# 7-Gyroscope.net
KiCad netlist of a schematic drawn in Altium Designer
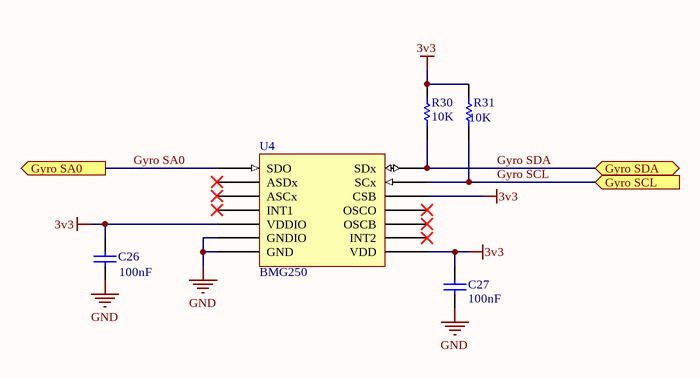
[diagram p0: 7-Gyroscope.SchDoc]

(export (version "E")
  (design (tool "Eeschema 10.0.6"))
  (components
    (comp (ref "C26")
      (value "100nF")
      (footprint "CAPC1608X90X30ML10T20")
      (description "Chip Capacitor, 100 nF, +/- 10%, 50 V, -55 to 125 degC, 0603 (1608 Metric), RoHS, Tape and Reel")
      (fields (field (name "VOLTAGE") "50Vdc") (field (name "MANUFACTURER") "SamsungElectro-Mechanics"))
      (libsource (lib "Altium Content Vault") (part "CAP-NP-2"))
    )
    (comp (ref "C27")
      (value "100nF")
      (footprint "CAPC1608X90X30ML10T20")
      (description "Chip Capacitor, 100 nF, +/- 10%, 50 V, -55 to 125 degC, 0603 (1608 Metric), RoHS, Tape and Reel")
      (fields (field (name "VOLTAGE") "50Vdc") (field (name "MANUFACTURER") "SamsungElectro-Mechanics"))
      (libsource (lib "Altium Content Vault") (part "CAP-NP-2"))
    )
    (comp (ref "R30")
      (value "10K")
      (footprint "RESC0603(1608)_N")
      (description "10K 0.1W 5% 0603 (1608 Metric)  SMD")
      (fields (field (name "TOLERANCE") "5 %") (field (name "POWER") "0.1 W"))
      (libsource (lib "Altium Content Vault") (part "RES"))
    )
    (comp (ref "R31")
      (value "10K")
      (footprint "RESC0603(1608)_N")
      (description "10K 0.1W 5% 0603 (1608 Metric)  SMD")
      (fields (field (name "TOLERANCE") "5 %") (field (name "POWER") "0.1 W"))
      (libsource (lib "Altium Content Vault") (part "RES"))
    )
    (comp (ref "U4")
      (value "BMG250")
      (footprint "BMG250")
      (description "3 Axis Gyroscope")
      (libsource (lib "VCB20") (part "BMG250"))
    )
  )
  (nets
    (net (code "1") (name "/Gyro SA0") (class "Default")
      (node (ref "U4") (pin "1") (pinfunction "SDO_1") (pintype "input"))
    )
    (net (code "2") (name "/Gyro SCL") (class "Default")
      (node (ref "R31") (pin "1") (pinfunction "1_1") (pintype "passive"))
      (node (ref "U4") (pin "13") (pinfunction "SCx_13") (pintype "input"))
    )
    (net (code "3") (name "/Gyro SDA") (class "Default")
      (node (ref "R30") (pin "1") (pinfunction "1_1") (pintype "passive"))
      (node (ref "U4") (pin "14") (pinfunction "SDx_14") (pintype "bidirectional"))
    )
    (net (code "4") (name "3v3") (class "Default")
      (node (ref "C26") (pin "2") (pinfunction "2_2") (pintype "passive"))
      (node (ref "C27") (pin "2") (pinfunction "2_2") (pintype "passive"))
      (node (ref "R30") (pin "2") (pinfunction "2_2") (pintype "passive"))
      (node (ref "R31") (pin "2") (pinfunction "2_2") (pintype "passive"))
      (node (ref "U4") (pin "12") (pinfunction "CSB_12") (pintype "passive"))
      (node (ref "U4") (pin "5") (pinfunction "VDDIO_5") (pintype "power_in"))
      (node (ref "U4") (pin "8") (pinfunction "VDD_8") (pintype "power_in"))
    )
    (net (code "5") (name "GND") (class "Default")
      (node (ref "C26") (pin "1") (pinfunction "1_1") (pintype "passive"))
      (node (ref "C27") (pin "1") (pinfunction "1_1") (pintype "passive"))
      (node (ref "U4") (pin "6") (pinfunction "GNDIO_6") (pintype "power_in"))
      (node (ref "U4") (pin "7") (pinfunction "GND_7") (pintype "power_in"))
    )
    (net (code "6") (name "unconnected-(U4-ASCx-Pad3)") (class "Default")
      (node (ref "U4") (pin "3") (pinfunction "ASCx_3") (pintype "passive+no_connect"))
    )
    (net (code "7") (name "unconnected-(U4-ASDx-Pad2)") (class "Default")
      (node (ref "U4") (pin "2") (pinfunction "ASDx_2") (pintype "passive+no_connect"))
    )
    (net (code "8") (name "unconnected-(U4-INT1-Pad4)") (class "Default")
      (node (ref "U4") (pin "4") (pinfunction "INT1_4") (pintype "passive+no_connect"))
    )
    (net (code "9") (name "unconnected-(U4-INT2-Pad9)") (class "Default")
      (node (ref "U4") (pin "9") (pinfunction "INT2_9") (pintype "passive+no_connect"))
    )
    (net (code "10") (name "unconnected-(U4-OSCB-Pad10)") (class "Default")
      (node (ref "U4") (pin "10") (pinfunction "OSCB_10") (pintype "passive+no_connect"))
    )
    (net (code "11") (name "unconnected-(U4-OSCO-Pad11)") (class "Default")
      (node (ref "U4") (pin "11") (pinfunction "OSCO_11") (pintype "passive+no_connect"))
    )
  )
)
